# memext.net
KiCad netlist of a schematic drawn in EAGLE
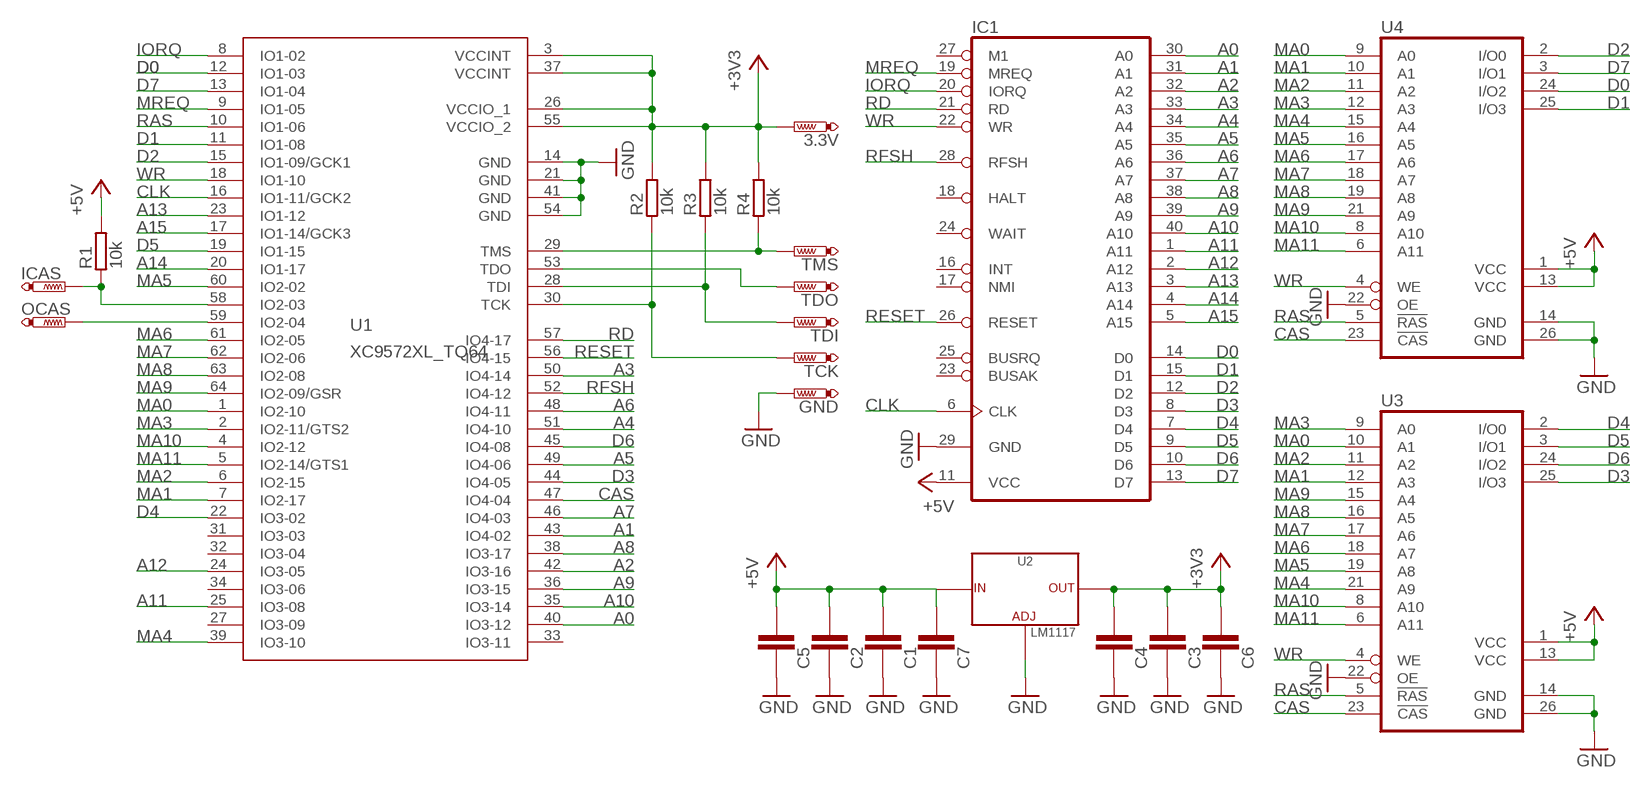
[diagram p0: schematic, sheet 1]

(export (version "E")
  (design (tool "Eeschema 10.0.6"))
  (components
    (comp (ref "3.3V")
      (value "PTR1TP15SQ")
      (footprint "eagle-import:TP15SQ")
      (libsource (lib "eagle-import") (part "PTR1TP15SQ"))
    )
    (comp (ref "C1")
      (value "KONDENZATORYC0603")
      (footprint "eagle-import:0603")
      (libsource (lib "eagle-import") (part "KONDENZATORYC0603"))
    )
    (comp (ref "C2")
      (value "KONDENZATORYC0603")
      (footprint "eagle-import:0603")
      (libsource (lib "eagle-import") (part "KONDENZATORYC0603"))
    )
    (comp (ref "C3")
      (value "KONDENZATORYC0603")
      (footprint "eagle-import:0603")
      (libsource (lib "eagle-import") (part "KONDENZATORYC0603"))
    )
    (comp (ref "C4")
      (value "KONDENZATORYC0603")
      (footprint "eagle-import:0603")
      (libsource (lib "eagle-import") (part "KONDENZATORYC0603"))
    )
    (comp (ref "C5")
      (value "KONDENZATORYC0603")
      (footprint "eagle-import:0603")
      (libsource (lib "eagle-import") (part "KONDENZATORYC0603"))
    )
    (comp (ref "C6")
      (value "KONDENZATORYC0603")
      (footprint "eagle-import:0603")
      (libsource (lib "eagle-import") (part "KONDENZATORYC0603"))
    )
    (comp (ref "C7")
      (value "KONDENZATORYC0603")
      (footprint "eagle-import:0603")
      (libsource (lib "eagle-import") (part "KONDENZATORYC0603"))
    )
    (comp (ref "GND")
      (value "PTR1TP15SQ")
      (footprint "eagle-import:TP15SQ")
      (libsource (lib "eagle-import") (part "PTR1TP15SQ"))
    )
    (comp (ref "IC1")
      (value "Z80CPU")
      (footprint "eagle-import:DIL40")
      (libsource (lib "eagle-import") (part "Z80CPU"))
    )
    (comp (ref "ICAS")
      (value "PTR1TP15SQ")
      (footprint "eagle-import:TP15SQ")
      (libsource (lib "eagle-import") (part "PTR1TP15SQ"))
    )
    (comp (ref "OCAS")
      (value "PTR1TP15SQ")
      (footprint "eagle-import:TP15SQ")
      (libsource (lib "eagle-import") (part "PTR1TP15SQ"))
    )
    (comp (ref "R1")
      (value "10k")
      (footprint "eagle-import:0603")
      (libsource (lib "eagle-import") (part "ODPORYR0603"))
    )
    (comp (ref "R2")
      (value "10k")
      (footprint "eagle-import:0603")
      (libsource (lib "eagle-import") (part "ODPORYR0603"))
    )
    (comp (ref "R3")
      (value "10k")
      (footprint "eagle-import:0603")
      (libsource (lib "eagle-import") (part "ODPORYR0603"))
    )
    (comp (ref "R4")
      (value "10k")
      (footprint "eagle-import:0603")
      (libsource (lib "eagle-import") (part "ODPORYR0603"))
    )
    (comp (ref "TCK")
      (value "PTR1TP15SQ")
      (footprint "eagle-import:TP15SQ")
      (libsource (lib "eagle-import") (part "PTR1TP15SQ"))
    )
    (comp (ref "TDI")
      (value "PTR1TP15SQ")
      (footprint "eagle-import:TP15SQ")
      (libsource (lib "eagle-import") (part "PTR1TP15SQ"))
    )
    (comp (ref "TDO")
      (value "PTR1TP15SQ")
      (footprint "eagle-import:TP15SQ")
      (libsource (lib "eagle-import") (part "PTR1TP15SQ"))
    )
    (comp (ref "TMS")
      (value "PTR1TP15SQ")
      (footprint "eagle-import:TP15SQ")
      (libsource (lib "eagle-import") (part "PTR1TP15SQ"))
    )
    (comp (ref "U1")
      (value "XC9572XL_TQ64")
      (footprint "eagle-import:TQ-64")
      (libsource (lib "eagle-import") (part "XC9572XL_TQ64"))
    )
    (comp (ref "U2")
      (value "LM1117")
      (footprint "eagle-import:SOT-223")
      (libsource (lib "eagle-import") (part "LM1117"))
    )
    (comp (ref "U3")
      (value "DRAM4X4")
      (footprint "eagle-import:SOJ26-24")
      (libsource (lib "eagle-import") (part "DRAM4X4"))
    )
    (comp (ref "U4")
      (value "DRAM4X4")
      (footprint "eagle-import:SOJ26-24")
      (libsource (lib "eagle-import") (part "DRAM4X4"))
    )
  )
  (nets
    (net (code "1") (name "+3V3") (class "Default")
      (node (ref "3.3V") (pin "TP") (pinfunction "TP_TP") (pintype "input"))
      (node (ref "C3") (pin "2") (pinfunction "P$2_2") (pintype "bidirectional"))
      (node (ref "C4") (pin "2") (pinfunction "P$2_2") (pintype "bidirectional"))
      (node (ref "C6") (pin "2") (pinfunction "P$2_2") (pintype "bidirectional"))
      (node (ref "R2") (pin "2") (pinfunction "P$2_2") (pintype "bidirectional"))
      (node (ref "R3") (pin "2") (pinfunction "P$2_2") (pintype "bidirectional"))
      (node (ref "R4") (pin "2") (pinfunction "P$2_2") (pintype "bidirectional"))
      (node (ref "U1") (pin "26") (pinfunction "VCCIO_1_26") (pintype "passive"))
      (node (ref "U1") (pin "3") (pinfunction "VCCINT_3") (pintype "passive"))
      (node (ref "U1") (pin "37") (pinfunction "VCCINT_37") (pintype "passive"))
      (node (ref "U1") (pin "55") (pinfunction "VCCIO_2_55") (pintype "passive"))
      (node (ref "U2") (pin "2") (pinfunction "OUT_2") (pintype "output"))
      (node (ref "U2") (pin "4") (pinfunction "OUT_4") (pintype "output"))
    )
    (net (code "2") (name "+5V") (class "Default")
      (node (ref "C1") (pin "2") (pinfunction "P$2_2") (pintype "bidirectional"))
      (node (ref "C2") (pin "2") (pinfunction "P$2_2") (pintype "bidirectional"))
      (node (ref "C5") (pin "2") (pinfunction "P$2_2") (pintype "bidirectional"))
      (node (ref "C7") (pin "2") (pinfunction "P$2_2") (pintype "bidirectional"))
      (node (ref "IC1") (pin "11") (pinfunction "VCC_11") (pintype "power_in"))
      (node (ref "R1") (pin "2") (pinfunction "P$2_2") (pintype "bidirectional"))
      (node (ref "U2") (pin "3") (pinfunction "IN_3") (pintype "input"))
      (node (ref "U3") (pin "1") (pinfunction "VCC_1") (pintype "bidirectional"))
      (node (ref "U3") (pin "13") (pinfunction "VCC_13") (pintype "bidirectional"))
      (node (ref "U4") (pin "1") (pinfunction "VCC_1") (pintype "bidirectional"))
      (node (ref "U4") (pin "13") (pinfunction "VCC_13") (pintype "bidirectional"))
    )
    (net (code "3") (name "/A0") (class "Default")
      (node (ref "IC1") (pin "30") (pinfunction "A0_30") (pintype "output"))
      (node (ref "U1") (pin "40") (pinfunction "IO3-12_40") (pintype "bidirectional"))
    )
    (net (code "4") (name "/A1") (class "Default")
      (node (ref "IC1") (pin "31") (pinfunction "A1_31") (pintype "output"))
      (node (ref "U1") (pin "43") (pinfunction "IO4-02_43") (pintype "bidirectional"))
    )
    (net (code "5") (name "/A2") (class "Default")
      (node (ref "IC1") (pin "32") (pinfunction "A2_32") (pintype "output"))
      (node (ref "U1") (pin "42") (pinfunction "IO3-16_42") (pintype "bidirectional"))
    )
    (net (code "6") (name "/A3") (class "Default")
      (node (ref "IC1") (pin "33") (pinfunction "A3_33") (pintype "output"))
      (node (ref "U1") (pin "50") (pinfunction "IO4-14_50") (pintype "bidirectional"))
    )
    (net (code "7") (name "/A4") (class "Default")
      (node (ref "IC1") (pin "34") (pinfunction "A4_34") (pintype "output"))
      (node (ref "U1") (pin "51") (pinfunction "IO4-10_51") (pintype "bidirectional"))
    )
    (net (code "8") (name "/A5") (class "Default")
      (node (ref "IC1") (pin "35") (pinfunction "A5_35") (pintype "output"))
      (node (ref "U1") (pin "49") (pinfunction "IO4-06_49") (pintype "bidirectional"))
    )
    (net (code "9") (name "/A6") (class "Default")
      (node (ref "IC1") (pin "36") (pinfunction "A6_36") (pintype "output"))
      (node (ref "U1") (pin "48") (pinfunction "IO4-11_48") (pintype "bidirectional"))
    )
    (net (code "10") (name "/A7") (class "Default")
      (node (ref "IC1") (pin "37") (pinfunction "A7_37") (pintype "output"))
      (node (ref "U1") (pin "46") (pinfunction "IO4-03_46") (pintype "bidirectional"))
    )
    (net (code "11") (name "/A8") (class "Default")
      (node (ref "IC1") (pin "38") (pinfunction "A8_38") (pintype "output"))
      (node (ref "U1") (pin "38") (pinfunction "IO3-17_38") (pintype "bidirectional"))
    )
    (net (code "12") (name "/A9") (class "Default")
      (node (ref "IC1") (pin "39") (pinfunction "A9_39") (pintype "output"))
      (node (ref "U1") (pin "36") (pinfunction "IO3-15_36") (pintype "bidirectional"))
    )
    (net (code "13") (name "/A10") (class "Default")
      (node (ref "IC1") (pin "40") (pinfunction "A10_40") (pintype "output"))
      (node (ref "U1") (pin "35") (pinfunction "IO3-14_35") (pintype "bidirectional"))
    )
    (net (code "14") (name "/A11") (class "Default")
      (node (ref "IC1") (pin "1") (pinfunction "A11_1") (pintype "output"))
      (node (ref "U1") (pin "25") (pinfunction "IO3-08_25") (pintype "bidirectional"))
    )
    (net (code "15") (name "/A12") (class "Default")
      (node (ref "IC1") (pin "2") (pinfunction "A12_2") (pintype "output"))
      (node (ref "U1") (pin "24") (pinfunction "IO3-05_24") (pintype "bidirectional"))
    )
    (net (code "16") (name "/A13") (class "Default")
      (node (ref "IC1") (pin "3") (pinfunction "A13_3") (pintype "output"))
      (node (ref "U1") (pin "23") (pinfunction "IO1-12_23") (pintype "bidirectional"))
    )
    (net (code "17") (name "/A14") (class "Default")
      (node (ref "IC1") (pin "4") (pinfunction "A14_4") (pintype "output"))
      (node (ref "U1") (pin "20") (pinfunction "IO1-17_20") (pintype "bidirectional"))
    )
    (net (code "18") (name "/A15") (class "Default")
      (node (ref "IC1") (pin "5") (pinfunction "A15_5") (pintype "output"))
      (node (ref "U1") (pin "17") (pinfunction "IO1-14/GCK3_17") (pintype "bidirectional"))
    )
    (net (code "19") (name "/CAS") (class "Default")
      (node (ref "U1") (pin "47") (pinfunction "IO4-04_47") (pintype "bidirectional"))
      (node (ref "U3") (pin "23") (pinfunction "~{CAS}_23") (pintype "input"))
      (node (ref "U4") (pin "23") (pinfunction "~{CAS}_23") (pintype "input"))
    )
    (net (code "20") (name "/CLK") (class "Default")
      (node (ref "IC1") (pin "6") (pinfunction "CLK_6") (pintype "input"))
      (node (ref "U1") (pin "16") (pinfunction "IO1-11/GCK2_16") (pintype "bidirectional"))
    )
    (net (code "21") (name "/D0") (class "Default")
      (node (ref "IC1") (pin "14") (pinfunction "D0_14") (pintype "bidirectional"))
      (node (ref "U1") (pin "12") (pinfunction "IO1-03_12") (pintype "bidirectional"))
      (node (ref "U4") (pin "24") (pinfunction "I/O2_24") (pintype "bidirectional"))
    )
    (net (code "22") (name "/D1") (class "Default")
      (node (ref "IC1") (pin "15") (pinfunction "D1_15") (pintype "bidirectional"))
      (node (ref "U1") (pin "11") (pinfunction "IO1-08_11") (pintype "bidirectional"))
      (node (ref "U4") (pin "25") (pinfunction "I/O3_25") (pintype "bidirectional"))
    )
    (net (code "23") (name "/D2") (class "Default")
      (node (ref "IC1") (pin "12") (pinfunction "D2_12") (pintype "bidirectional"))
      (node (ref "U1") (pin "15") (pinfunction "IO1-09/GCK1_15") (pintype "bidirectional"))
      (node (ref "U4") (pin "2") (pinfunction "I/O0_2") (pintype "bidirectional"))
    )
    (net (code "24") (name "/D3") (class "Default")
      (node (ref "IC1") (pin "8") (pinfunction "D3_8") (pintype "bidirectional"))
      (node (ref "U1") (pin "44") (pinfunction "IO4-05_44") (pintype "bidirectional"))
      (node (ref "U3") (pin "25") (pinfunction "I/O3_25") (pintype "bidirectional"))
    )
    (net (code "25") (name "/D4") (class "Default")
      (node (ref "IC1") (pin "7") (pinfunction "D4_7") (pintype "bidirectional"))
      (node (ref "U1") (pin "22") (pinfunction "IO3-02_22") (pintype "bidirectional"))
      (node (ref "U3") (pin "2") (pinfunction "I/O0_2") (pintype "bidirectional"))
    )
    (net (code "26") (name "/D5") (class "Default")
      (node (ref "IC1") (pin "9") (pinfunction "D5_9") (pintype "bidirectional"))
      (node (ref "U1") (pin "19") (pinfunction "IO1-15_19") (pintype "bidirectional"))
      (node (ref "U3") (pin "3") (pinfunction "I/O1_3") (pintype "bidirectional"))
    )
    (net (code "27") (name "/D6") (class "Default")
      (node (ref "IC1") (pin "10") (pinfunction "D6_10") (pintype "bidirectional"))
      (node (ref "U1") (pin "45") (pinfunction "IO4-08_45") (pintype "bidirectional"))
      (node (ref "U3") (pin "24") (pinfunction "I/O2_24") (pintype "bidirectional"))
    )
    (net (code "28") (name "/D7") (class "Default")
      (node (ref "IC1") (pin "13") (pinfunction "D7_13") (pintype "bidirectional"))
      (node (ref "U1") (pin "13") (pinfunction "IO1-04_13") (pintype "bidirectional"))
      (node (ref "U4") (pin "3") (pinfunction "I/O1_3") (pintype "bidirectional"))
    )
    (net (code "29") (name "/IORQ") (class "Default")
      (node (ref "IC1") (pin "20") (pinfunction "IORQ_20") (pintype "output"))
      (node (ref "U1") (pin "8") (pinfunction "IO1-02_8") (pintype "bidirectional"))
    )
    (net (code "30") (name "/MA0") (class "Default")
      (node (ref "U1") (pin "1") (pinfunction "IO2-10_1") (pintype "bidirectional"))
      (node (ref "U3") (pin "10") (pinfunction "A1_10") (pintype "input"))
      (node (ref "U4") (pin "9") (pinfunction "A0_9") (pintype "input"))
    )
    (net (code "31") (name "/MA1") (class "Default")
      (node (ref "U1") (pin "7") (pinfunction "IO2-17_7") (pintype "bidirectional"))
      (node (ref "U3") (pin "12") (pinfunction "A3_12") (pintype "input"))
      (node (ref "U4") (pin "10") (pinfunction "A1_10") (pintype "input"))
    )
    (net (code "32") (name "/MA2") (class "Default")
      (node (ref "U1") (pin "6") (pinfunction "IO2-15_6") (pintype "bidirectional"))
      (node (ref "U3") (pin "11") (pinfunction "A2_11") (pintype "input"))
      (node (ref "U4") (pin "11") (pinfunction "A2_11") (pintype "input"))
    )
    (net (code "33") (name "/MA3") (class "Default")
      (node (ref "U1") (pin "2") (pinfunction "IO2-11/GTS2_2") (pintype "bidirectional"))
      (node (ref "U3") (pin "9") (pinfunction "A0_9") (pintype "input"))
      (node (ref "U4") (pin "12") (pinfunction "A3_12") (pintype "input"))
    )
    (net (code "34") (name "/MA4") (class "Default")
      (node (ref "U1") (pin "39") (pinfunction "IO3-10_39") (pintype "bidirectional"))
      (node (ref "U3") (pin "21") (pinfunction "A9_21") (pintype "input"))
      (node (ref "U4") (pin "15") (pinfunction "A4_15") (pintype "input"))
    )
    (net (code "35") (name "/MA5") (class "Default")
      (node (ref "U1") (pin "60") (pinfunction "IO2-02_60") (pintype "bidirectional"))
      (node (ref "U3") (pin "19") (pinfunction "A8_19") (pintype "input"))
      (node (ref "U4") (pin "16") (pinfunction "A5_16") (pintype "input"))
    )
    (net (code "36") (name "/MA6") (class "Default")
      (node (ref "U1") (pin "61") (pinfunction "IO2-05_61") (pintype "bidirectional"))
      (node (ref "U3") (pin "18") (pinfunction "A7_18") (pintype "input"))
      (node (ref "U4") (pin "17") (pinfunction "A6_17") (pintype "input"))
    )
    (net (code "37") (name "/MA7") (class "Default")
      (node (ref "U1") (pin "62") (pinfunction "IO2-06_62") (pintype "bidirectional"))
      (node (ref "U3") (pin "17") (pinfunction "A6_17") (pintype "input"))
      (node (ref "U4") (pin "18") (pinfunction "A7_18") (pintype "input"))
    )
    (net (code "38") (name "/MA8") (class "Default")
      (node (ref "U1") (pin "63") (pinfunction "IO2-08_63") (pintype "bidirectional"))
      (node (ref "U3") (pin "16") (pinfunction "A5_16") (pintype "input"))
      (node (ref "U4") (pin "19") (pinfunction "A8_19") (pintype "input"))
    )
    (net (code "39") (name "/MA9") (class "Default")
      (node (ref "U1") (pin "64") (pinfunction "IO2-09/GSR_64") (pintype "bidirectional"))
      (node (ref "U3") (pin "15") (pinfunction "A4_15") (pintype "input"))
      (node (ref "U4") (pin "21") (pinfunction "A9_21") (pintype "input"))
    )
    (net (code "40") (name "/MA10") (class "Default")
      (node (ref "U1") (pin "4") (pinfunction "IO2-12_4") (pintype "bidirectional"))
      (node (ref "U3") (pin "8") (pinfunction "A10_8") (pintype "input"))
      (node (ref "U4") (pin "8") (pinfunction "A10_8") (pintype "input"))
    )
    (net (code "41") (name "/MA11") (class "Default")
      (node (ref "U1") (pin "5") (pinfunction "IO2-14/GTS1_5") (pintype "bidirectional"))
      (node (ref "U3") (pin "6") (pinfunction "A11_6") (pintype "input"))
      (node (ref "U4") (pin "6") (pinfunction "A11_6") (pintype "input"))
    )
    (net (code "42") (name "/MREQ") (class "Default")
      (node (ref "IC1") (pin "19") (pinfunction "MREQ_19") (pintype "output"))
      (node (ref "U1") (pin "9") (pinfunction "IO1-05_9") (pintype "bidirectional"))
    )
    (net (code "43") (name "/RAS") (class "Default")
      (node (ref "U1") (pin "10") (pinfunction "IO1-06_10") (pintype "bidirectional"))
      (node (ref "U3") (pin "5") (pinfunction "~{RAS}_5") (pintype "input"))
      (node (ref "U4") (pin "5") (pinfunction "~{RAS}_5") (pintype "input"))
    )
    (net (code "44") (name "/RD") (class "Default")
      (node (ref "IC1") (pin "21") (pinfunction "RD_21") (pintype "output"))
      (node (ref "U1") (pin "57") (pinfunction "IO4-17_57") (pintype "bidirectional"))
    )
    (net (code "45") (name "/RESET") (class "Default")
      (node (ref "IC1") (pin "26") (pinfunction "RESET_26") (pintype "input"))
      (node (ref "U1") (pin "56") (pinfunction "IO4-15_56") (pintype "bidirectional"))
    )
    (net (code "46") (name "/RFSH") (class "Default")
      (node (ref "IC1") (pin "28") (pinfunction "RFSH_28") (pintype "output"))
      (node (ref "U1") (pin "52") (pinfunction "IO4-12_52") (pintype "bidirectional"))
    )
    (net (code "47") (name "/WR") (class "Default")
      (node (ref "IC1") (pin "22") (pinfunction "WR_22") (pintype "output"))
      (node (ref "U1") (pin "18") (pinfunction "IO1-10_18") (pintype "bidirectional"))
      (node (ref "U3") (pin "4") (pinfunction "WE_4") (pintype "input"))
      (node (ref "U4") (pin "4") (pinfunction "WE_4") (pintype "input"))
    )
    (net (code "48") (name "GND") (class "Default")
      (node (ref "C1") (pin "1") (pinfunction "P$1_1") (pintype "bidirectional"))
      (node (ref "C2") (pin "1") (pinfunction "P$1_1") (pintype "bidirectional"))
      (node (ref "C3") (pin "1") (pinfunction "P$1_1") (pintype "bidirectional"))
      (node (ref "C4") (pin "1") (pinfunction "P$1_1") (pintype "bidirectional"))
      (node (ref "C5") (pin "1") (pinfunction "P$1_1") (pintype "bidirectional"))
      (node (ref "C6") (pin "1") (pinfunction "P$1_1") (pintype "bidirectional"))
      (node (ref "C7") (pin "1") (pinfunction "P$1_1") (pintype "bidirectional"))
      (node (ref "GND") (pin "TP") (pinfunction "TP_TP") (pintype "input"))
      (node (ref "IC1") (pin "29") (pinfunction "GND_29") (pintype "power_in"))
      (node (ref "U1") (pin "14") (pinfunction "GND_14") (pintype "passive"))
      (node (ref "U1") (pin "21") (pinfunction "GND_21") (pintype "passive"))
      (node (ref "U1") (pin "41") (pinfunction "GND_41") (pintype "passive"))
      (node (ref "U1") (pin "54") (pinfunction "GND_54") (pintype "passive"))
      (node (ref "U2") (pin "1") (pinfunction "ADJ_1") (pintype "input"))
      (node (ref "U3") (pin "14") (pinfunction "GND_14") (pintype "bidirectional"))
      (node (ref "U3") (pin "22") (pinfunction "OE_22") (pintype "input"))
      (node (ref "U3") (pin "26") (pinfunction "GND_26") (pintype "bidirectional"))
      (node (ref "U4") (pin "14") (pinfunction "GND_14") (pintype "bidirectional"))
      (node (ref "U4") (pin "22") (pinfunction "OE_22") (pintype "input"))
      (node (ref "U4") (pin "26") (pinfunction "GND_26") (pintype "bidirectional"))
    )
    (net (code "49") (name "Net-(R1-P$1)") (class "Default")
      (node (ref "ICAS") (pin "TP") (pinfunction "TP_TP") (pintype "input"))
      (node (ref "R1") (pin "1") (pinfunction "P$1_1") (pintype "bidirectional"))
      (node (ref "U1") (pin "58") (pinfunction "IO2-03_58") (pintype "bidirectional"))
    )
    (net (code "50") (name "Net-(R2-P$1)") (class "Default")
      (node (ref "R2") (pin "1") (pinfunction "P$1_1") (pintype "bidirectional"))
      (node (ref "TCK") (pin "TP") (pinfunction "TP_TP") (pintype "input"))
      (node (ref "U1") (pin "30") (pinfunction "TCK_30") (pintype "input"))
    )
    (net (code "51") (name "Net-(R3-P$1)") (class "Default")
      (node (ref "R3") (pin "1") (pinfunction "P$1_1") (pintype "bidirectional"))
      (node (ref "TDI") (pin "TP") (pinfunction "TP_TP") (pintype "input"))
      (node (ref "U1") (pin "28") (pinfunction "TDI_28") (pintype "input"))
    )
    (net (code "52") (name "Net-(R4-P$1)") (class "Default")
      (node (ref "R4") (pin "1") (pinfunction "P$1_1") (pintype "bidirectional"))
      (node (ref "TMS") (pin "TP") (pinfunction "TP_TP") (pintype "input"))
      (node (ref "U1") (pin "29") (pinfunction "TMS_29") (pintype "input"))
    )
    (net (code "53") (name "Net-(U1-IO2-04)") (class "Default")
      (node (ref "OCAS") (pin "TP") (pinfunction "TP_TP") (pintype "input"))
      (node (ref "U1") (pin "59") (pinfunction "IO2-04_59") (pintype "bidirectional"))
    )
    (net (code "54") (name "Net-(U1-TDO)") (class "Default")
      (node (ref "TDO") (pin "TP") (pinfunction "TP_TP") (pintype "input"))
      (node (ref "U1") (pin "53") (pinfunction "TDO_53") (pintype "output"))
    )
    (net (code "55") (name "unconnected-(IC1-BUSAK-Pad23)") (class "Default")
      (node (ref "IC1") (pin "23") (pinfunction "BUSAK_23") (pintype "output"))
    )
    (net (code "56") (name "unconnected-(IC1-BUSRQ-Pad25)") (class "Default")
      (node (ref "IC1") (pin "25") (pinfunction "BUSRQ_25") (pintype "input"))
    )
    (net (code "57") (name "unconnected-(IC1-HALT-Pad18)") (class "Default")
      (node (ref "IC1") (pin "18") (pinfunction "HALT_18") (pintype "output"))
    )
    (net (code "58") (name "unconnected-(IC1-INT-Pad16)") (class "Default")
      (node (ref "IC1") (pin "16") (pinfunction "INT_16") (pintype "input"))
    )
    (net (code "59") (name "unconnected-(IC1-M1-Pad27)") (class "Default")
      (node (ref "IC1") (pin "27") (pinfunction "M1_27") (pintype "output"))
    )
    (net (code "60") (name "unconnected-(IC1-NMI-Pad17)") (class "Default")
      (node (ref "IC1") (pin "17") (pinfunction "NMI_17") (pintype "input"))
    )
    (net (code "61") (name "unconnected-(IC1-WAIT-Pad24)") (class "Default")
      (node (ref "IC1") (pin "24") (pinfunction "WAIT_24") (pintype "input"))
    )
    (net (code "62") (name "unconnected-(U1-IO3-03-Pad31)") (class "Default")
      (node (ref "U1") (pin "31") (pinfunction "IO3-03_31") (pintype "bidirectional"))
    )
    (net (code "63") (name "unconnected-(U1-IO3-04-Pad32)") (class "Default")
      (node (ref "U1") (pin "32") (pinfunction "IO3-04_32") (pintype "bidirectional"))
    )
    (net (code "64") (name "unconnected-(U1-IO3-06-Pad34)") (class "Default")
      (node (ref "U1") (pin "34") (pinfunction "IO3-06_34") (pintype "bidirectional"))
    )
    (net (code "65") (name "unconnected-(U1-IO3-09-Pad27)") (class "Default")
      (node (ref "U1") (pin "27") (pinfunction "IO3-09_27") (pintype "bidirectional"))
    )
    (net (code "66") (name "unconnected-(U1-IO3-11-Pad33)") (class "Default")
      (node (ref "U1") (pin "33") (pinfunction "IO3-11_33") (pintype "bidirectional"))
    )
  )
)
